# audio_hat.net
KiCad netlist of a schematic drawn in EAGLE
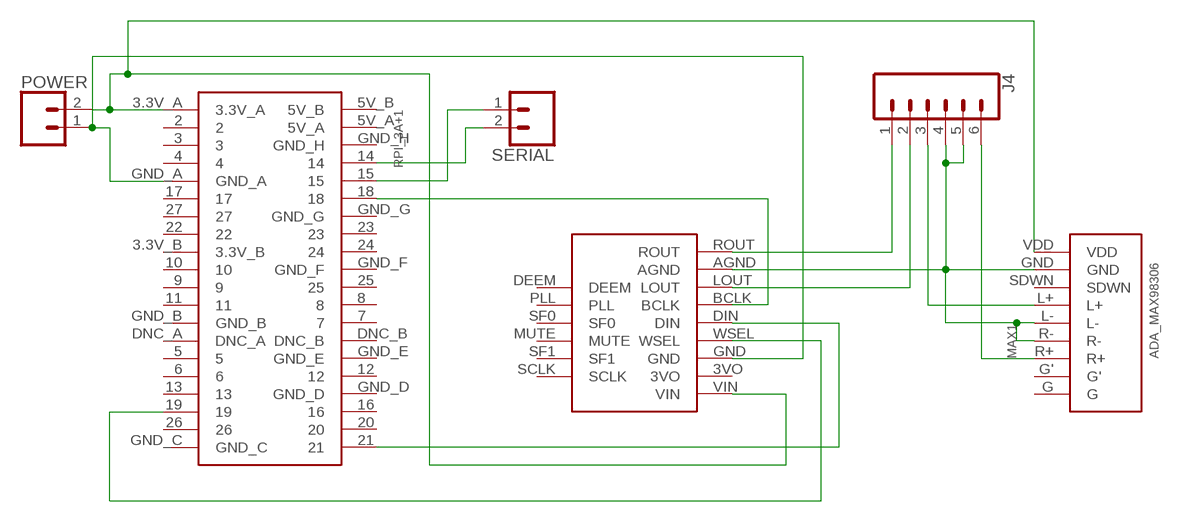
[diagram p0: schematic, sheet 1]

(export (version "E")
  (design (tool "Eeschema 10.0.6"))
  (components
    (comp (ref "J4")
      (value "CONN_06NO_SILK_NO_POP")
      (footprint "eagle-import:1X06_NO_SILK")
      (libsource (lib "eagle-import") (part "CONN_06NO_SILK_NO_POP"))
    )
    (comp (ref "MAX1")
      (value "ADA_MAX98306")
      (footprint "eagle-import:ADA_MAX98306")
      (libsource (lib "eagle-import") (part "ADA_MAX98306"))
    )
    (comp (ref "POWER")
      (value "CONN_02")
      (footprint "eagle-import:1X02")
      (libsource (lib "eagle-import") (part "CONN_02"))
    )
    (comp (ref "RPI_3A+1")
      (value "RPI_3A+")
      (footprint "eagle-import:RPI_3A+")
      (libsource (lib "eagle-import") (part "RPI_3A+"))
    )
    (comp (ref "SERIAL")
      (value "CONN_02")
      (footprint "eagle-import:1X02")
      (libsource (lib "eagle-import") (part "CONN_02"))
    )
    (comp (ref "UDA1")
      (value "ADA_UDA1334")
      (footprint "eagle-import:ADA_UDA1334")
      (libsource (lib "eagle-import") (part "ADA_UDA1334"))
    )
  )
  (nets
    (net (code "1") (name "Net-(J4-Pad1)") (class "Default")
      (node (ref "J4") (pin "1") (pinfunction "1_1") (pintype "passive"))
      (node (ref "UDA1") (pin "ROUT") (pinfunction "ROUT_ROUT") (pintype "bidirectional"))
    )
    (net (code "2") (name "Net-(J4-Pad2)") (class "Default")
      (node (ref "J4") (pin "2") (pinfunction "2_2") (pintype "passive"))
      (node (ref "UDA1") (pin "LOUT") (pinfunction "LOUT_LOUT") (pintype "bidirectional"))
    )
    (net (code "3") (name "Net-(J4-Pad3)") (class "Default")
      (node (ref "J4") (pin "3") (pinfunction "3_3") (pintype "passive"))
      (node (ref "MAX1") (pin "L+") (pinfunction "L+_L+") (pintype "bidirectional"))
    )
    (net (code "4") (name "Net-(J4-Pad4)") (class "Default")
      (node (ref "J4") (pin "4") (pinfunction "4_4") (pintype "passive"))
      (node (ref "J4") (pin "5") (pinfunction "5_5") (pintype "passive"))
      (node (ref "MAX1") (pin "GND") (pinfunction "GND_GND") (pintype "bidirectional"))
      (node (ref "MAX1") (pin "L-") (pinfunction "L-_L-") (pintype "bidirectional"))
      (node (ref "MAX1") (pin "R-") (pinfunction "R-_R-") (pintype "bidirectional"))
      (node (ref "UDA1") (pin "AGND") (pinfunction "AGND_AGND") (pintype "bidirectional"))
    )
    (net (code "5") (name "Net-(J4-Pad6)") (class "Default")
      (node (ref "J4") (pin "6") (pinfunction "6_6") (pintype "passive"))
      (node (ref "MAX1") (pin "R+") (pinfunction "R+_R+") (pintype "bidirectional"))
    )
    (net (code "6") (name "Net-(MAX1-PadVDD)") (class "Default")
      (node (ref "MAX1") (pin "VDD") (pinfunction "VDD_VDD") (pintype "bidirectional"))
      (node (ref "POWER") (pin "2") (pinfunction "2_2") (pintype "passive"))
      (node (ref "RPI_3A+1") (pin "3.3V_A") (pinfunction "3.3V_A_3.3V_A") (pintype "bidirectional"))
      (node (ref "UDA1") (pin "VIN") (pinfunction "VIN_VIN") (pintype "bidirectional"))
    )
    (net (code "7") (name "Net-(POWER-Pad1)") (class "Default")
      (node (ref "POWER") (pin "1") (pinfunction "1_1") (pintype "passive"))
      (node (ref "RPI_3A+1") (pin "GND_A") (pinfunction "GND_A_GND_A") (pintype "bidirectional"))
      (node (ref "UDA1") (pin "GND") (pinfunction "GND_GND") (pintype "bidirectional"))
    )
    (net (code "8") (name "Net-(RPI_3A+1-Pad14)") (class "Default")
      (node (ref "RPI_3A+1") (pin "14") (pinfunction "14_14") (pintype "bidirectional"))
      (node (ref "SERIAL") (pin "2") (pinfunction "2_2") (pintype "passive"))
    )
    (net (code "9") (name "Net-(RPI_3A+1-Pad15)") (class "Default")
      (node (ref "RPI_3A+1") (pin "15") (pinfunction "15_15") (pintype "bidirectional"))
      (node (ref "SERIAL") (pin "1") (pinfunction "1_1") (pintype "passive"))
    )
    (net (code "10") (name "Net-(RPI_3A+1-Pad18)") (class "Default")
      (node (ref "RPI_3A+1") (pin "18") (pinfunction "18_18") (pintype "bidirectional"))
      (node (ref "UDA1") (pin "BCLK") (pinfunction "BCLK_BCLK") (pintype "bidirectional"))
    )
    (net (code "11") (name "Net-(RPI_3A+1-Pad19)") (class "Default")
      (node (ref "RPI_3A+1") (pin "19") (pinfunction "19_19") (pintype "bidirectional"))
      (node (ref "UDA1") (pin "WSEL") (pinfunction "WSEL_WSEL") (pintype "bidirectional"))
    )
    (net (code "12") (name "Net-(RPI_3A+1-Pad21)") (class "Default")
      (node (ref "RPI_3A+1") (pin "21") (pinfunction "21_21") (pintype "bidirectional"))
      (node (ref "UDA1") (pin "DIN") (pinfunction "DIN_DIN") (pintype "bidirectional"))
    )
    (net (code "13") (name "unconnected-(MAX1-PadG')") (class "Default")
      (node (ref "MAX1") (pin "G'") (pinfunction "G'_G'") (pintype "bidirectional"))
    )
    (net (code "14") (name "unconnected-(MAX1-PadG)") (class "Default")
      (node (ref "MAX1") (pin "G") (pinfunction "G_G") (pintype "bidirectional"))
    )
    (net (code "15") (name "unconnected-(MAX1-PadSDWN)") (class "Default")
      (node (ref "MAX1") (pin "SDWN") (pinfunction "SDWN_SDWN") (pintype "bidirectional"))
    )
    (net (code "16") (name "unconnected-(RPI_3A+1-Pad2)") (class "Default")
      (node (ref "RPI_3A+1") (pin "2") (pinfunction "2_2") (pintype "bidirectional"))
    )
    (net (code "17") (name "unconnected-(RPI_3A+1-Pad3)") (class "Default")
      (node (ref "RPI_3A+1") (pin "3") (pinfunction "3_3") (pintype "bidirectional"))
    )
    (net (code "18") (name "unconnected-(RPI_3A+1-Pad3.3V_B)") (class "Default")
      (node (ref "RPI_3A+1") (pin "3.3V_B") (pinfunction "3.3V_B_3.3V_B") (pintype "bidirectional"))
    )
    (net (code "19") (name "unconnected-(RPI_3A+1-Pad4)") (class "Default")
      (node (ref "RPI_3A+1") (pin "4") (pinfunction "4_4") (pintype "bidirectional"))
    )
    (net (code "20") (name "unconnected-(RPI_3A+1-Pad5)") (class "Default")
      (node (ref "RPI_3A+1") (pin "5") (pinfunction "5_5") (pintype "bidirectional"))
    )
    (net (code "21") (name "unconnected-(RPI_3A+1-Pad5V_A)") (class "Default")
      (node (ref "RPI_3A+1") (pin "5V_A") (pinfunction "5V_A_5V_A") (pintype "bidirectional"))
    )
    (net (code "22") (name "unconnected-(RPI_3A+1-Pad5V_B)") (class "Default")
      (node (ref "RPI_3A+1") (pin "5V_B") (pinfunction "5V_B_5V_B") (pintype "bidirectional"))
    )
    (net (code "23") (name "unconnected-(RPI_3A+1-Pad6)") (class "Default")
      (node (ref "RPI_3A+1") (pin "6") (pinfunction "6_6") (pintype "bidirectional"))
    )
    (net (code "24") (name "unconnected-(RPI_3A+1-Pad7)") (class "Default")
      (node (ref "RPI_3A+1") (pin "7") (pinfunction "7_7") (pintype "bidirectional"))
    )
    (net (code "25") (name "unconnected-(RPI_3A+1-Pad8)") (class "Default")
      (node (ref "RPI_3A+1") (pin "8") (pinfunction "8_8") (pintype "bidirectional"))
    )
    (net (code "26") (name "unconnected-(RPI_3A+1-Pad9)") (class "Default")
      (node (ref "RPI_3A+1") (pin "9") (pinfunction "9_9") (pintype "bidirectional"))
    )
    (net (code "27") (name "unconnected-(RPI_3A+1-Pad10)") (class "Default")
      (node (ref "RPI_3A+1") (pin "10") (pinfunction "10_10") (pintype "bidirectional"))
    )
    (net (code "28") (name "unconnected-(RPI_3A+1-Pad11)") (class "Default")
      (node (ref "RPI_3A+1") (pin "11") (pinfunction "11_11") (pintype "bidirectional"))
    )
    (net (code "29") (name "unconnected-(RPI_3A+1-Pad12)") (class "Default")
      (node (ref "RPI_3A+1") (pin "12") (pinfunction "12_12") (pintype "bidirectional"))
    )
    (net (code "30") (name "unconnected-(RPI_3A+1-Pad13)") (class "Default")
      (node (ref "RPI_3A+1") (pin "13") (pinfunction "13_13") (pintype "bidirectional"))
    )
    (net (code "31") (name "unconnected-(RPI_3A+1-Pad16)") (class "Default")
      (node (ref "RPI_3A+1") (pin "16") (pinfunction "16_16") (pintype "bidirectional"))
    )
    (net (code "32") (name "unconnected-(RPI_3A+1-Pad17)") (class "Default")
      (node (ref "RPI_3A+1") (pin "17") (pinfunction "17_17") (pintype "bidirectional"))
    )
    (net (code "33") (name "unconnected-(RPI_3A+1-Pad20)") (class "Default")
      (node (ref "RPI_3A+1") (pin "20") (pinfunction "20_20") (pintype "bidirectional"))
    )
    (net (code "34") (name "unconnected-(RPI_3A+1-Pad22)") (class "Default")
      (node (ref "RPI_3A+1") (pin "22") (pinfunction "22_22") (pintype "bidirectional"))
    )
    (net (code "35") (name "unconnected-(RPI_3A+1-Pad23)") (class "Default")
      (node (ref "RPI_3A+1") (pin "23") (pinfunction "23_23") (pintype "bidirectional"))
    )
    (net (code "36") (name "unconnected-(RPI_3A+1-Pad24)") (class "Default")
      (node (ref "RPI_3A+1") (pin "24") (pinfunction "24_24") (pintype "bidirectional"))
    )
    (net (code "37") (name "unconnected-(RPI_3A+1-Pad25)") (class "Default")
      (node (ref "RPI_3A+1") (pin "25") (pinfunction "25_25") (pintype "bidirectional"))
    )
    (net (code "38") (name "unconnected-(RPI_3A+1-Pad26)") (class "Default")
      (node (ref "RPI_3A+1") (pin "26") (pinfunction "26_26") (pintype "bidirectional"))
    )
    (net (code "39") (name "unconnected-(RPI_3A+1-Pad27)") (class "Default")
      (node (ref "RPI_3A+1") (pin "27") (pinfunction "27_27") (pintype "bidirectional"))
    )
    (net (code "40") (name "unconnected-(RPI_3A+1-PadDNC_A)") (class "Default")
      (node (ref "RPI_3A+1") (pin "DNC_A") (pinfunction "DNC_A_DNC_A") (pintype "bidirectional"))
    )
    (net (code "41") (name "unconnected-(RPI_3A+1-PadDNC_B)") (class "Default")
      (node (ref "RPI_3A+1") (pin "DNC_B") (pinfunction "DNC_B_DNC_B") (pintype "bidirectional"))
    )
    (net (code "42") (name "unconnected-(RPI_3A+1-PadGND_B)") (class "Default")
      (node (ref "RPI_3A+1") (pin "GND_B") (pinfunction "GND_B_GND_B") (pintype "bidirectional"))
    )
    (net (code "43") (name "unconnected-(RPI_3A+1-PadGND_C)") (class "Default")
      (node (ref "RPI_3A+1") (pin "GND_C") (pinfunction "GND_C_GND_C") (pintype "bidirectional"))
    )
    (net (code "44") (name "unconnected-(RPI_3A+1-PadGND_D)") (class "Default")
      (node (ref "RPI_3A+1") (pin "GND_D") (pinfunction "GND_D_GND_D") (pintype "bidirectional"))
    )
    (net (code "45") (name "unconnected-(RPI_3A+1-PadGND_E)") (class "Default")
      (node (ref "RPI_3A+1") (pin "GND_E") (pinfunction "GND_E_GND_E") (pintype "bidirectional"))
    )
    (net (code "46") (name "unconnected-(RPI_3A+1-PadGND_F)") (class "Default")
      (node (ref "RPI_3A+1") (pin "GND_F") (pinfunction "GND_F_GND_F") (pintype "bidirectional"))
    )
    (net (code "47") (name "unconnected-(RPI_3A+1-PadGND_G)") (class "Default")
      (node (ref "RPI_3A+1") (pin "GND_G") (pinfunction "GND_G_GND_G") (pintype "bidirectional"))
    )
    (net (code "48") (name "unconnected-(RPI_3A+1-PadGND_H)") (class "Default")
      (node (ref "RPI_3A+1") (pin "GND_H") (pinfunction "GND_H_GND_H") (pintype "bidirectional"))
    )
    (net (code "49") (name "unconnected-(UDA1-Pad3VO)") (class "Default")
      (node (ref "UDA1") (pin "3VO") (pinfunction "3VO_3VO") (pintype "bidirectional"))
    )
    (net (code "50") (name "unconnected-(UDA1-PadDEEM)") (class "Default")
      (node (ref "UDA1") (pin "DEEM") (pinfunction "DEEM_DEEM") (pintype "bidirectional"))
    )
    (net (code "51") (name "unconnected-(UDA1-PadMUTE)") (class "Default")
      (node (ref "UDA1") (pin "MUTE") (pinfunction "MUTE_MUTE") (pintype "bidirectional"))
    )
    (net (code "52") (name "unconnected-(UDA1-PadPLL)") (class "Default")
      (node (ref "UDA1") (pin "PLL") (pinfunction "PLL_PLL") (pintype "bidirectional"))
    )
    (net (code "53") (name "unconnected-(UDA1-PadSCLK)") (class "Default")
      (node (ref "UDA1") (pin "SCLK") (pinfunction "SCLK_SCLK") (pintype "bidirectional"))
    )
    (net (code "54") (name "unconnected-(UDA1-PadSF0)") (class "Default")
      (node (ref "UDA1") (pin "SF0") (pinfunction "SF0_SF0") (pintype "bidirectional"))
    )
    (net (code "55") (name "unconnected-(UDA1-PadSF1)") (class "Default")
      (node (ref "UDA1") (pin "SF1") (pinfunction "SF1_SF1") (pintype "bidirectional"))
    )
  )
)
